# rpi-pwrbtn.net
KiCad netlist of a schematic drawn in EAGLE
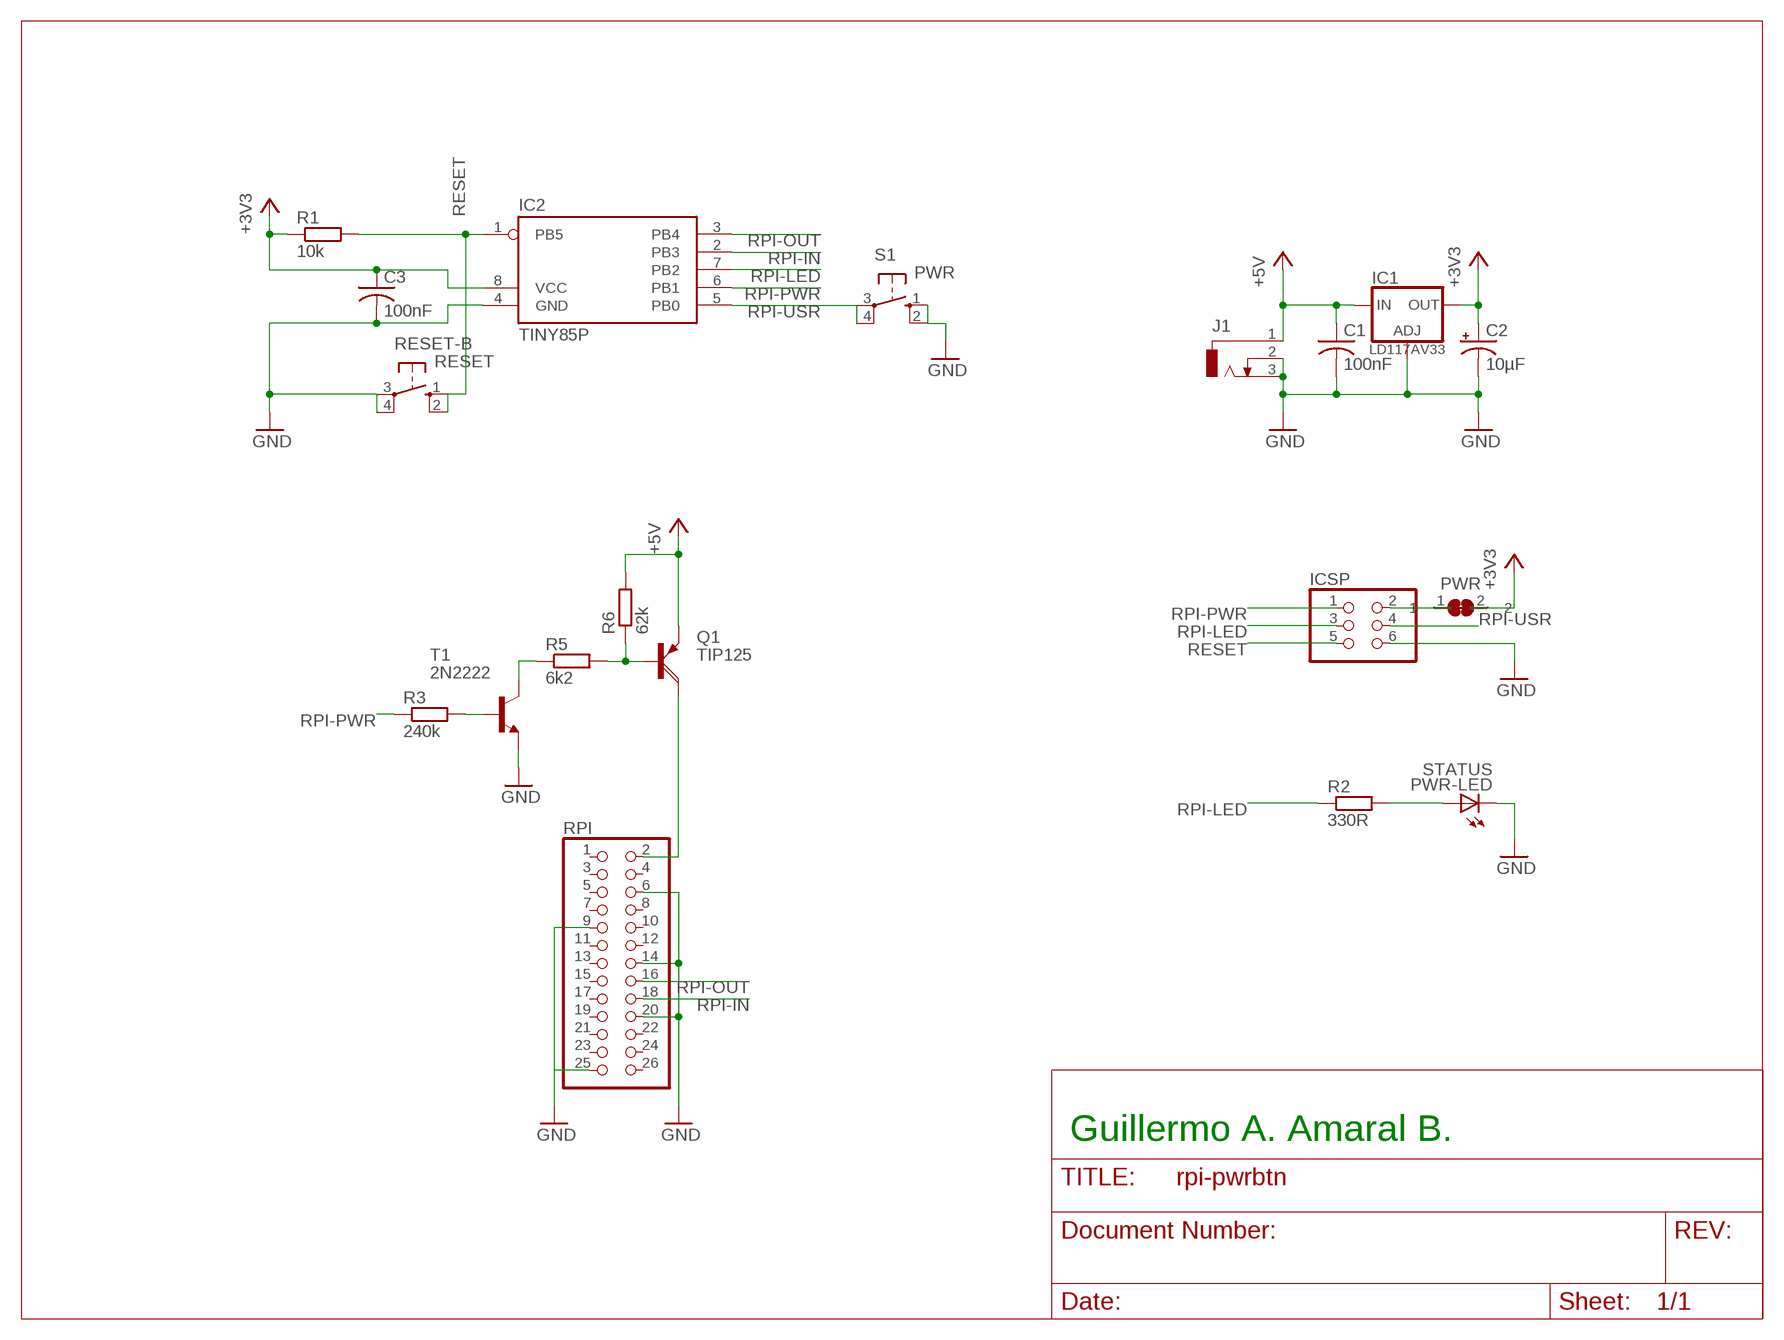
[diagram p0: schematic, sheet 1]

(export (version "E")
  (design (tool "Eeschema 10.0.6"))
  (components
    (comp (ref "C1")
      (value "100nF")
      (footprint "eagle-import:C050-024X044")
      (libsource (lib "eagle-import") (part "C-US050-024X044"))
    )
    (comp (ref "C2")
      (value "10µF")
      (footprint "eagle-import:E2,5-6E")
      (libsource (lib "eagle-import") (part "CPOL-USE2,5-6E"))
    )
    (comp (ref "C3")
      (value "100nF")
      (footprint "eagle-import:C050-024X044")
      (libsource (lib "eagle-import") (part "C-US050-024X044"))
    )
    (comp (ref "IC1")
      (value "LD117AV33")
      (footprint "eagle-import:TO220L1")
      (libsource (lib "eagle-import") (part "LD117A?V33"))
    )
    (comp (ref "IC2")
      (value "TINY85P")
      (footprint "eagle-import:DIL08")
      (libsource (lib "eagle-import") (part "TINY85P"))
    )
    (comp (ref "ICSP")
      (value "PINHD-2X3")
      (footprint "eagle-import:2X03")
      (libsource (lib "eagle-import") (part "PINHD-2X3"))
    )
    (comp (ref "J1")
      (value "DCJ0303")
      (footprint "eagle-import:DCJ0303")
      (libsource (lib "eagle-import") (part "DCJ0303"))
    )
    (comp (ref "PWR")
      (value "SJ-BRIDGED")
      (footprint "eagle-import:SJ-BRIDGED")
      (libsource (lib "eagle-import") (part "SJ-BRIDGED"))
    )
    (comp (ref "PWR-LED")
      (value "STATUS")
      (footprint "eagle-import:LED5MM")
      (libsource (lib "eagle-import") (part "LED5MM"))
    )
    (comp (ref "Q1")
      (value "TIP125")
      (footprint "eagle-import:TO220AH")
      (libsource (lib "eagle-import") (part "TIP125"))
    )
    (comp (ref "R1")
      (value "10k")
      (footprint "eagle-import:0204_7")
      (libsource (lib "eagle-import") (part "R-EU_0204/7"))
    )
    (comp (ref "R2")
      (value "330R")
      (footprint "eagle-import:0204_7")
      (libsource (lib "eagle-import") (part "R-EU_0204/7"))
    )
    (comp (ref "R3")
      (value "240k")
      (footprint "eagle-import:0204_7")
      (libsource (lib "eagle-import") (part "R-EU_0204/7"))
    )
    (comp (ref "R5")
      (value "6k2")
      (footprint "eagle-import:0204_7")
      (libsource (lib "eagle-import") (part "R-EU_0204/7"))
    )
    (comp (ref "R6")
      (value "62k")
      (footprint "eagle-import:0204_7")
      (libsource (lib "eagle-import") (part "R-EU_0204/7"))
    )
    (comp (ref "RESET-B")
      (value "RESET")
      (footprint "eagle-import:B3F-10XX")
      (fields (field (name "MPN") "B3F-1000"))
      (libsource (lib "eagle-import") (part "10-XX"))
    )
    (comp (ref "RPI")
      (value "PINHD-2X13")
      (footprint "eagle-import:2X13")
      (libsource (lib "eagle-import") (part "PINHD-2X13"))
    )
    (comp (ref "S1")
      (value "PWR")
      (footprint "eagle-import:B3F-10XX")
      (fields (field (name "MPN") "B3F-1000"))
      (libsource (lib "eagle-import") (part "10-XX"))
    )
    (comp (ref "T1")
      (value "2N2222")
      (footprint "eagle-import:TO18")
      (libsource (lib "eagle-import") (part "2N2222"))
    )
  )
  (nets
    (net (code "1") (name "+3V3") (class "Default")
      (node (ref "C2") (pin "+") (pinfunction "+_+") (pintype "passive"))
      (node (ref "C3") (pin "1") (pinfunction "1_1") (pintype "passive"))
      (node (ref "IC1") (pin "2") (pinfunction "OUT_2") (pintype "passive"))
      (node (ref "IC2") (pin "8") (pinfunction "VCC_8") (pintype "power_in"))
      (node (ref "PWR") (pin "2") (pinfunction "2_2") (pintype "bidirectional"))
      (node (ref "R1") (pin "1") (pinfunction "1_1") (pintype "passive"))
    )
    (net (code "2") (name "+5V") (class "Default")
      (node (ref "C1") (pin "1") (pinfunction "1_1") (pintype "passive"))
      (node (ref "IC1") (pin "3") (pinfunction "IN_3") (pintype "input"))
      (node (ref "J1") (pin "1") (pinfunction "1_1") (pintype "passive"))
      (node (ref "Q1") (pin "E") (pinfunction "E_E") (pintype "passive"))
      (node (ref "R6") (pin "2") (pinfunction "2_2") (pintype "passive"))
    )
    (net (code "3") (name "/RESET") (class "Default")
      (node (ref "IC2") (pin "1") (pinfunction "PB5_1") (pintype "bidirectional"))
      (node (ref "ICSP") (pin "5") (pinfunction "5_5") (pintype "passive"))
      (node (ref "R1") (pin "2") (pinfunction "2_2") (pintype "passive"))
      (node (ref "RESET-B") (pin "1") (pinfunction "S_1") (pintype "passive"))
      (node (ref "RESET-B") (pin "2") (pinfunction "S1_2") (pintype "passive"))
    )
    (net (code "4") (name "/RPI-IN") (class "Default")
      (node (ref "IC2") (pin "2") (pinfunction "PB3_2") (pintype "bidirectional"))
      (node (ref "RPI") (pin "18") (pinfunction "18_18") (pintype "passive"))
    )
    (net (code "5") (name "/RPI-LED") (class "Default")
      (node (ref "IC2") (pin "7") (pinfunction "PB2_7") (pintype "bidirectional"))
      (node (ref "ICSP") (pin "3") (pinfunction "3_3") (pintype "passive"))
      (node (ref "R2") (pin "1") (pinfunction "1_1") (pintype "passive"))
    )
    (net (code "6") (name "/RPI-OUT") (class "Default")
      (node (ref "IC2") (pin "3") (pinfunction "PB4_3") (pintype "bidirectional"))
      (node (ref "RPI") (pin "16") (pinfunction "16_16") (pintype "passive"))
    )
    (net (code "7") (name "/RPI-PWR") (class "Default")
      (node (ref "IC2") (pin "6") (pinfunction "PB1_6") (pintype "bidirectional"))
      (node (ref "ICSP") (pin "1") (pinfunction "1_1") (pintype "passive"))
      (node (ref "R3") (pin "1") (pinfunction "1_1") (pintype "passive"))
    )
    (net (code "8") (name "/RPI-USR") (class "Default")
      (node (ref "IC2") (pin "5") (pinfunction "PB0_5") (pintype "bidirectional"))
      (node (ref "ICSP") (pin "4") (pinfunction "4_4") (pintype "passive"))
      (node (ref "S1") (pin "3") (pinfunction "P_3") (pintype "passive"))
      (node (ref "S1") (pin "4") (pinfunction "P1_4") (pintype "passive"))
    )
    (net (code "9") (name "GND") (class "Default")
      (node (ref "C1") (pin "2") (pinfunction "2_2") (pintype "passive"))
      (node (ref "C2") (pin "-") (pinfunction "-_-") (pintype "passive"))
      (node (ref "C3") (pin "2") (pinfunction "2_2") (pintype "passive"))
      (node (ref "IC1") (pin "1") (pinfunction "ADJ_1") (pintype "input"))
      (node (ref "IC2") (pin "4") (pinfunction "GND_4") (pintype "power_in"))
      (node (ref "ICSP") (pin "6") (pinfunction "6_6") (pintype "passive"))
      (node (ref "J1") (pin "2") (pinfunction "2_2") (pintype "passive"))
      (node (ref "J1") (pin "3") (pinfunction "3_3") (pintype "passive"))
      (node (ref "PWR-LED") (pin "K") (pinfunction "C_K") (pintype "passive"))
      (node (ref "RESET-B") (pin "3") (pinfunction "P_3") (pintype "passive"))
      (node (ref "RESET-B") (pin "4") (pinfunction "P1_4") (pintype "passive"))
      (node (ref "RPI") (pin "14") (pinfunction "14_14") (pintype "passive"))
      (node (ref "RPI") (pin "20") (pinfunction "20_20") (pintype "passive"))
      (node (ref "RPI") (pin "25") (pinfunction "25_25") (pintype "passive"))
      (node (ref "RPI") (pin "6") (pinfunction "6_6") (pintype "passive"))
      (node (ref "RPI") (pin "9") (pinfunction "9_9") (pintype "passive"))
      (node (ref "S1") (pin "1") (pinfunction "S_1") (pintype "passive"))
      (node (ref "S1") (pin "2") (pinfunction "S1_2") (pintype "passive"))
      (node (ref "T1") (pin "1") (pinfunction "E_1") (pintype "passive"))
    )
    (net (code "10") (name "Net-(ICSP-Pad2)") (class "Default")
      (node (ref "ICSP") (pin "2") (pinfunction "2_2") (pintype "passive"))
      (node (ref "PWR") (pin "1") (pinfunction "1_1") (pintype "bidirectional"))
    )
    (net (code "11") (name "Net-(PWR-LED-PadA)") (class "Default")
      (node (ref "PWR-LED") (pin "A") (pinfunction "A_A") (pintype "passive"))
      (node (ref "R2") (pin "2") (pinfunction "2_2") (pintype "passive"))
    )
    (net (code "12") (name "Net-(Q1-PadB)") (class "Default")
      (node (ref "Q1") (pin "B") (pinfunction "B_B") (pintype "passive"))
      (node (ref "R5") (pin "2") (pinfunction "2_2") (pintype "passive"))
      (node (ref "R6") (pin "1") (pinfunction "1_1") (pintype "passive"))
    )
    (net (code "13") (name "Net-(Q1-PadC)") (class "Default")
      (node (ref "Q1") (pin "C") (pinfunction "C_C") (pintype "passive"))
      (node (ref "RPI") (pin "2") (pinfunction "2_2") (pintype "passive"))
    )
    (net (code "14") (name "Net-(T1-B)") (class "Default")
      (node (ref "R3") (pin "2") (pinfunction "2_2") (pintype "passive"))
      (node (ref "T1") (pin "2") (pinfunction "B_2") (pintype "passive"))
    )
    (net (code "15") (name "Net-(T1-C)") (class "Default")
      (node (ref "R5") (pin "1") (pinfunction "1_1") (pintype "passive"))
      (node (ref "T1") (pin "3") (pinfunction "C_3") (pintype "passive"))
    )
    (net (code "16") (name "unconnected-(RPI-Pad1)") (class "Default")
      (node (ref "RPI") (pin "1") (pinfunction "1_1") (pintype "passive"))
    )
    (net (code "17") (name "unconnected-(RPI-Pad3)") (class "Default")
      (node (ref "RPI") (pin "3") (pinfunction "3_3") (pintype "passive"))
    )
    (net (code "18") (name "unconnected-(RPI-Pad4)") (class "Default")
      (node (ref "RPI") (pin "4") (pinfunction "4_4") (pintype "passive"))
    )
    (net (code "19") (name "unconnected-(RPI-Pad5)") (class "Default")
      (node (ref "RPI") (pin "5") (pinfunction "5_5") (pintype "passive"))
    )
    (net (code "20") (name "unconnected-(RPI-Pad7)") (class "Default")
      (node (ref "RPI") (pin "7") (pinfunction "7_7") (pintype "passive"))
    )
    (net (code "21") (name "unconnected-(RPI-Pad8)") (class "Default")
      (node (ref "RPI") (pin "8") (pinfunction "8_8") (pintype "passive"))
    )
    (net (code "22") (name "unconnected-(RPI-Pad10)") (class "Default")
      (node (ref "RPI") (pin "10") (pinfunction "10_10") (pintype "passive"))
    )
    (net (code "23") (name "unconnected-(RPI-Pad11)") (class "Default")
      (node (ref "RPI") (pin "11") (pinfunction "11_11") (pintype "passive"))
    )
    (net (code "24") (name "unconnected-(RPI-Pad12)") (class "Default")
      (node (ref "RPI") (pin "12") (pinfunction "12_12") (pintype "passive"))
    )
    (net (code "25") (name "unconnected-(RPI-Pad13)") (class "Default")
      (node (ref "RPI") (pin "13") (pinfunction "13_13") (pintype "passive"))
    )
    (net (code "26") (name "unconnected-(RPI-Pad15)") (class "Default")
      (node (ref "RPI") (pin "15") (pinfunction "15_15") (pintype "passive"))
    )
    (net (code "27") (name "unconnected-(RPI-Pad17)") (class "Default")
      (node (ref "RPI") (pin "17") (pinfunction "17_17") (pintype "passive"))
    )
    (net (code "28") (name "unconnected-(RPI-Pad19)") (class "Default")
      (node (ref "RPI") (pin "19") (pinfunction "19_19") (pintype "passive"))
    )
    (net (code "29") (name "unconnected-(RPI-Pad21)") (class "Default")
      (node (ref "RPI") (pin "21") (pinfunction "21_21") (pintype "passive"))
    )
    (net (code "30") (name "unconnected-(RPI-Pad22)") (class "Default")
      (node (ref "RPI") (pin "22") (pinfunction "22_22") (pintype "passive"))
    )
    (net (code "31") (name "unconnected-(RPI-Pad23)") (class "Default")
      (node (ref "RPI") (pin "23") (pinfunction "23_23") (pintype "passive"))
    )
    (net (code "32") (name "unconnected-(RPI-Pad24)") (class "Default")
      (node (ref "RPI") (pin "24") (pinfunction "24_24") (pintype "passive"))
    )
    (net (code "33") (name "unconnected-(RPI-Pad26)") (class "Default")
      (node (ref "RPI") (pin "26") (pinfunction "26_26") (pintype "passive"))
    )
  )
)
